# Sheet3.net
KiCad netlist of a schematic drawn in Altium Designer
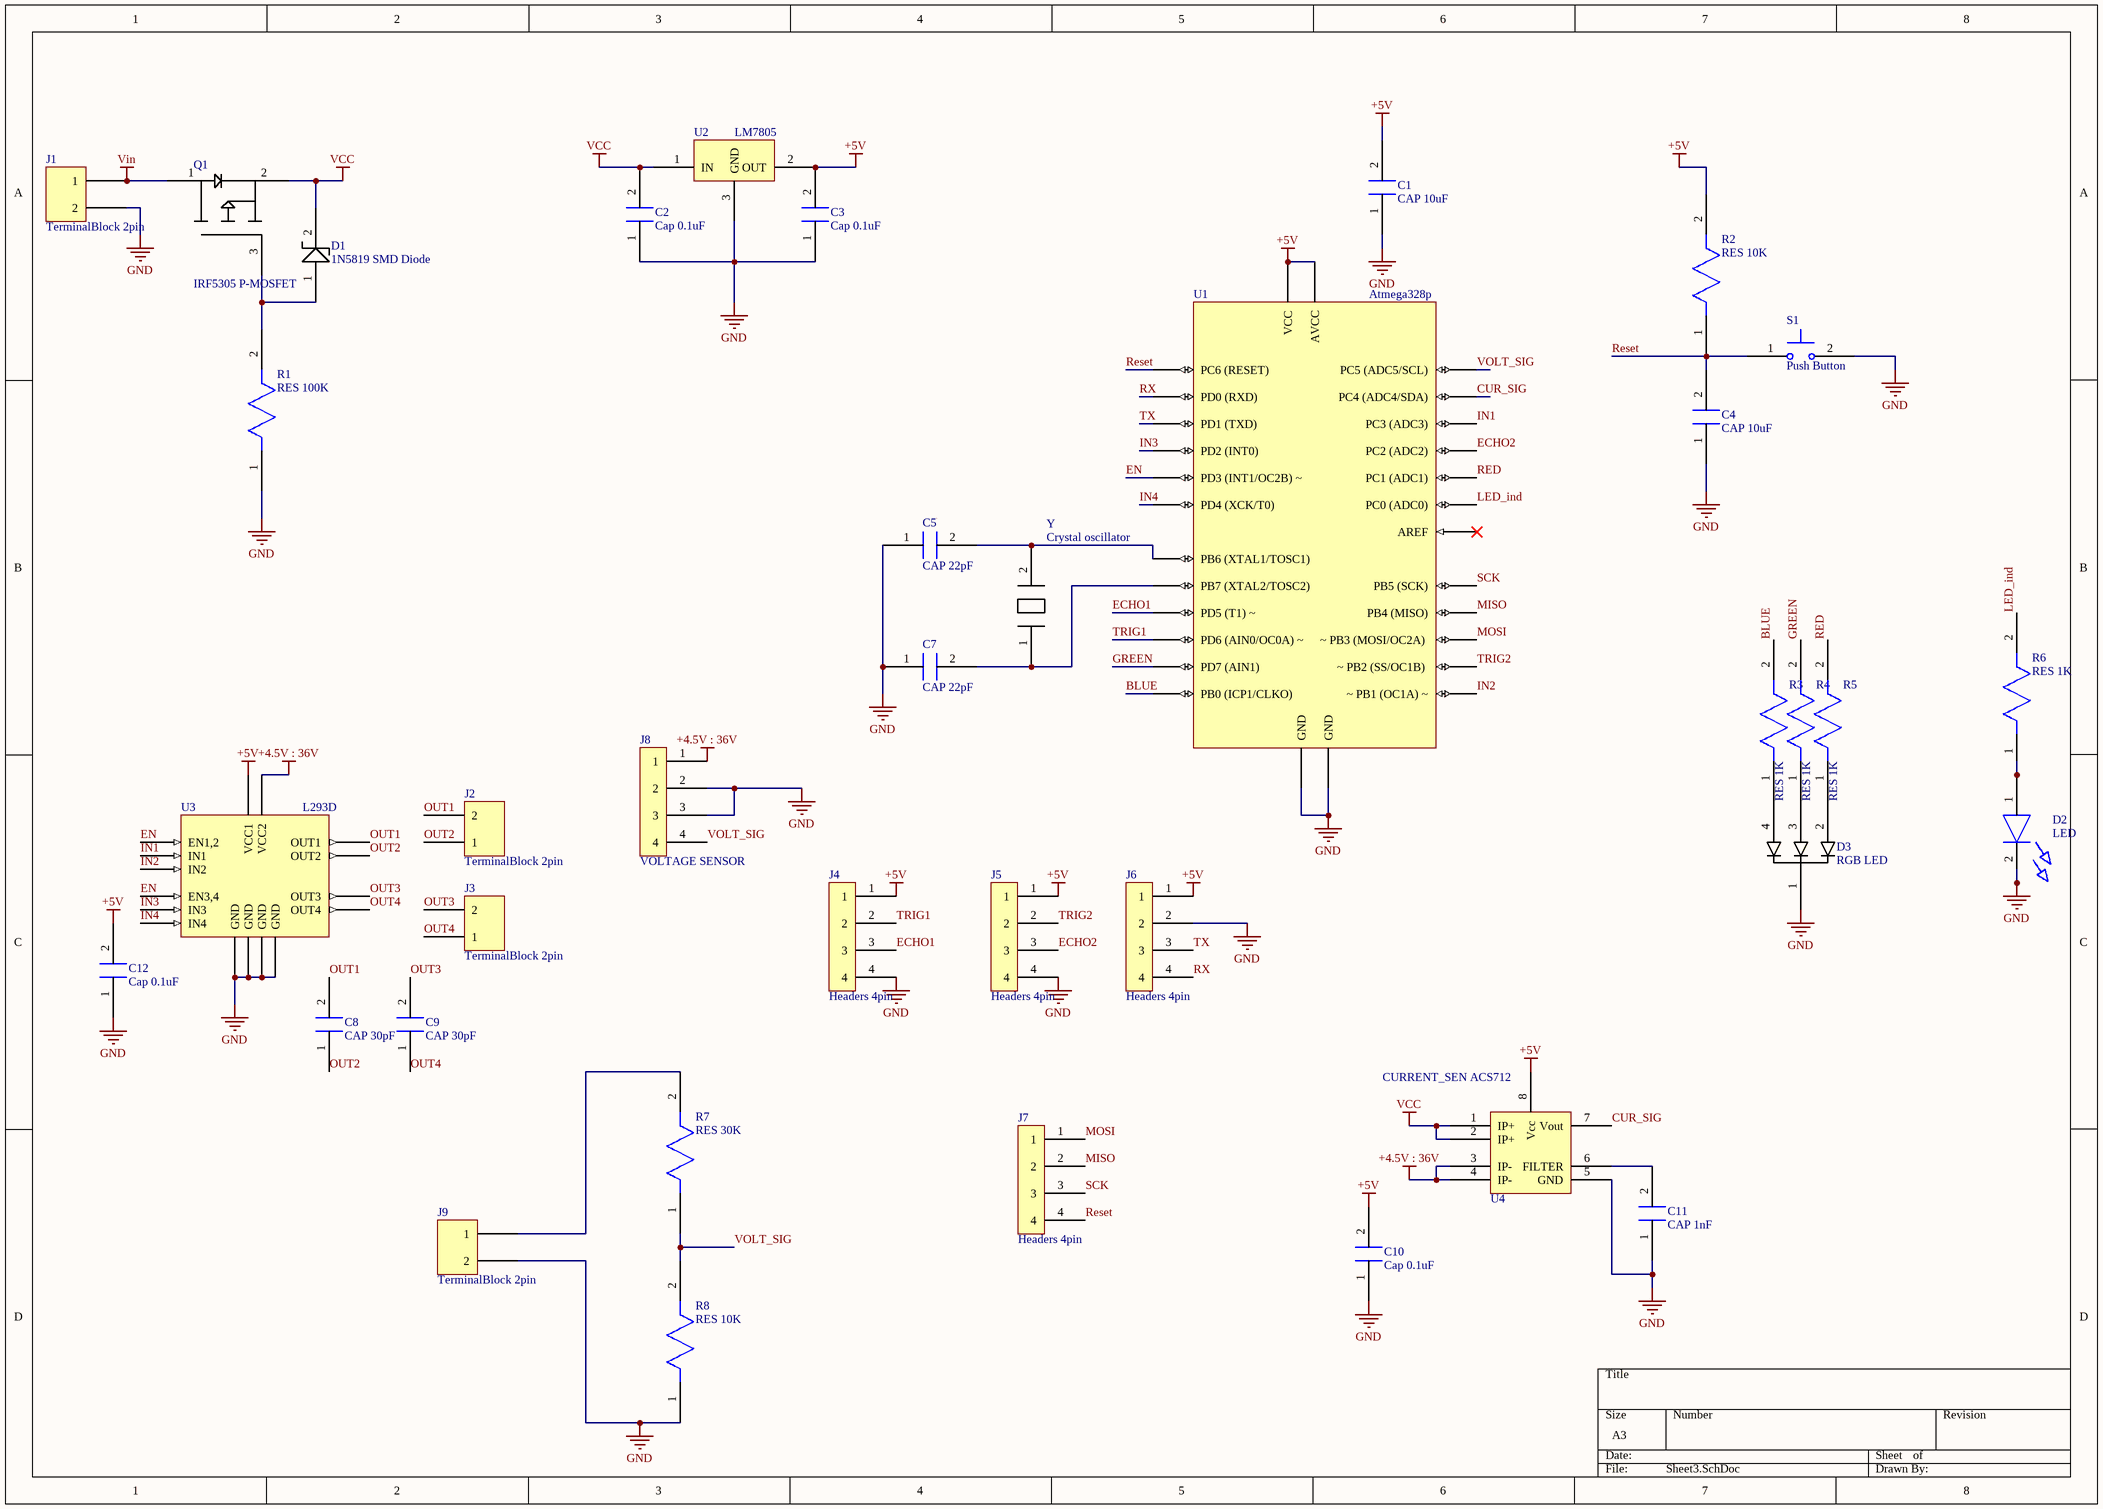
[diagram p0: Sheet3.SchDoc]

(export (version "E")
  (design (tool "Eeschema 10.0.6"))
  (components
    (comp (ref "C1") (value "CAP 10uF") (footprint "Cap 10uF") (libsource (lib "Schlib1") (part "CAP 10uF")))
    (comp (ref "C2")
      (value "Cap 0.1uF")
      (footprint "CAP 0.1uF")
      (libsource (lib "Schlib1") (part "Cap 0.1uF"))
    )
    (comp (ref "C3")
      (value "Cap 0.1uF")
      (footprint "CAP 0.1uF")
      (libsource (lib "Schlib1") (part "Cap 0.1uF"))
    )
    (comp (ref "C4") (value "CAP 10uF") (footprint "Cap 10uF") (libsource (lib "Schlib1") (part "CAP 10uF")))
    (comp (ref "C5") (value "CAP 22pF") (footprint "Cap 22pF") (libsource (lib "Schlib1") (part "CAP 22pF")))
    (comp (ref "C7") (value "CAP 22pF") (footprint "Cap 22pF") (libsource (lib "Schlib1") (part "CAP 22pF")))
    (comp (ref "C8") (value "CAP 30pF") (footprint "CAP 30pF") (libsource (lib "Schlib1") (part "CAP 30pF")))
    (comp (ref "C9") (value "CAP 30pF") (footprint "CAP 30pF") (libsource (lib "Schlib1") (part "CAP 30pF")))
    (comp (ref "C10")
      (value "Cap 0.1uF")
      (footprint "CAP 0.1uF")
      (libsource (lib "Schlib1") (part "Cap 0.1uF"))
    )
    (comp (ref "C11") (value "CAP 1nF") (footprint "CAP 1nF") (libsource (lib "Schlib1") (part "CAP 1nF")))
    (comp (ref "C12")
      (value "Cap 0.1uF")
      (footprint "CAP 0.1uF")
      (libsource (lib "Schlib1") (part "Cap 0.1uF"))
    )
    (comp (ref "D1")
      (value "1N5819 SMD Diode")
      (footprint "1N5819 SMD Diode")
      (libsource (lib "Schlib1") (part "1N5819 SMD Diode"))
    )
    (comp (ref "D2") (value "LED") (footprint "LED") (libsource (lib "Schlib1") (part "LED")))
    (comp (ref "D3") (value "RGB LED") (footprint "RGB LED") (libsource (lib "Schlib1") (part "RGB LED")))
    (comp (ref "J1")
      (value "TerminalBlock 2pin")
      (footprint "Terminal Block 2pin")
      (libsource (lib "Schlib1") (part "TerminalBlock 2pin"))
    )
    (comp (ref "J2")
      (value "TerminalBlock 2pin")
      (footprint "Terminal Block 2pin")
      (libsource (lib "") (part "TerminalBlock 2pin_1"))
    )
    (comp (ref "J3")
      (value "TerminalBlock 2pin")
      (footprint "Terminal Block 2pin")
      (libsource (lib "") (part "TerminalBlock 2pin_1"))
    )
    (comp (ref "J4")
      (value "Headers 4pin")
      (footprint "Header 4pin")
      (libsource (lib "Schlib1") (part "Headers 4pin"))
    )
    (comp (ref "J5")
      (value "Headers 4pin")
      (footprint "Header 4pin")
      (libsource (lib "Schlib1") (part "Headers 4pin"))
    )
    (comp (ref "J6")
      (value "Headers 4pin")
      (footprint "Header 4pin")
      (libsource (lib "Schlib1") (part "Headers 4pin"))
    )
    (comp (ref "J7")
      (value "Headers 4pin")
      (footprint "Header 4pin")
      (libsource (lib "Schlib1") (part "Headers 4pin"))
    )
    (comp (ref "J8")
      (value "VOLTAGE SENSOR")
      (footprint "Header 4pin")
      (libsource (lib "Schlib1") (part "Headers 4pin"))
    )
    (comp (ref "J9")
      (value "TerminalBlock 2pin")
      (footprint "Terminal Block 2pin")
      (libsource (lib "Schlib1") (part "TerminalBlock 2pin"))
    )
    (comp (ref "Q1")
      (value "IRF5305 P-MOSFET")
      (footprint "IRF5305")
      (libsource (lib "Schlib1") (part "IRF5305 P-MOSFET"))
    )
    (comp (ref "R1") (value "RES 100K") (footprint "Res100K") (libsource (lib "Schlib1") (part "RES 100K")))
    (comp (ref "R2") (value "RES 10K") (footprint "Res10K") (libsource (lib "Schlib1") (part "RES 10K")))
    (comp (ref "R3") (value "RES 1K") (footprint "Res 1K") (libsource (lib "Schlib1") (part "RES 1K")))
    (comp (ref "R4") (value "RES 1K") (footprint "Res 1K") (libsource (lib "Schlib1") (part "RES 1K")))
    (comp (ref "R5") (value "RES 1K") (footprint "Res 1K") (libsource (lib "Schlib1") (part "RES 1K")))
    (comp (ref "R6") (value "RES 1K") (footprint "Res 1K") (libsource (lib "Schlib1") (part "RES 1K")))
    (comp (ref "R7") (value "RES 30K") (footprint "Res100K") (libsource (lib "Schlib1") (part "RES 100K")))
    (comp (ref "R8") (value "RES 10K") (footprint "Res10K") (libsource (lib "Schlib1") (part "RES 10K")))
    (comp (ref "S1")
      (value "Push Button")
      (footprint "Push Button")
      (libsource (lib "Schlib1") (part "Push Button"))
    )
    (comp (ref "U1")
      (value "Atmega328p")
      (footprint "ATMega 328 P-PU - duplicate")
      (libsource (lib "Schlib1") (part "Atmega328p"))
    )
    (comp (ref "U2") (value "LM7805") (footprint "LM7805") (libsource (lib "Schlib1") (part "LM7805")))
    (comp (ref "U3") (value "L293D") (footprint "L293D") (libsource (lib "Schlib1") (part "L293D")))
    (comp (ref "U4")
      (value "CURRENT_SEN ACS712")
      (footprint "Cuurent_sens")
      (libsource (lib "Schlib1") (part "CURRENT_MOD ACS712"))
    )
    (comp (ref "Y")
      (value "Crystal oscillator")
      (footprint "Crrystal 16MHZ")
      (libsource (lib "Schlib1") (part "Crystal oscillator"))
    )
  )
  (nets
    (net (code "1") (name "+4.5V : 36V") (class "Default")
      (node (ref "J8") (pin "1") (pinfunction "1_1") (pintype "passive"))
      (node (ref "U3") (pin "8") (pinfunction "VCC2_8") (pintype "power_in"))
      (node (ref "U4") (pin "3") (pinfunction "IP-_3") (pintype "passive"))
      (node (ref "U4") (pin "4") (pinfunction "IP-_4") (pintype "passive"))
    )
    (net (code "2") (name "+5V") (class "Default")
      (node (ref "C1") (pin "2") (pinfunction "2_2") (pintype "passive"))
      (node (ref "C10") (pin "2") (pinfunction "2_2") (pintype "passive"))
      (node (ref "C12") (pin "2") (pinfunction "2_2") (pintype "passive"))
      (node (ref "C3") (pin "2") (pinfunction "2_2") (pintype "passive"))
      (node (ref "J4") (pin "1") (pinfunction "1_1") (pintype "passive"))
      (node (ref "J5") (pin "1") (pinfunction "1_1") (pintype "passive"))
      (node (ref "J6") (pin "1") (pinfunction "1_1") (pintype "passive"))
      (node (ref "R2") (pin "2") (pinfunction "4_2") (pintype "passive"))
      (node (ref "U1") (pin "20") (pinfunction "AVCC_20") (pintype "passive"))
      (node (ref "U1") (pin "7") (pinfunction "VCC_7") (pintype "passive"))
      (node (ref "U2") (pin "2") (pinfunction "OUT_2") (pintype "passive"))
      (node (ref "U3") (pin "16") (pinfunction "VCC1_16") (pintype "power_in"))
      (node (ref "U4") (pin "8") (pinfunction "Vcc_8") (pintype "passive"))
    )
    (net (code "4") (name "/BLUE") (class "Default")
      (node (ref "R3") (pin "2") (pinfunction "4_2") (pintype "passive"))
      (node (ref "U1") (pin "14") (pinfunction "PB0_(ICP1/CLKO)_14") (pintype "bidirectional"))
    )
    (net (code "5") (name "/CUR_SIG") (class "Default")
      (node (ref "U1") (pin "27") (pinfunction "PC4_(ADC4/SDA)_27") (pintype "bidirectional"))
      (node (ref "U4") (pin "7") (pinfunction "Vout_7") (pintype "passive"))
    )
    (net (code "6") (name "/ECHO1") (class "Default")
      (node (ref "J4") (pin "3") (pinfunction "3_3") (pintype "passive"))
      (node (ref "U1") (pin "11") (pinfunction "PD5_(T1)_~_11") (pintype "bidirectional"))
    )
    (net (code "7") (name "/ECHO2") (class "Default")
      (node (ref "J5") (pin "3") (pinfunction "3_3") (pintype "passive"))
      (node (ref "U1") (pin "25") (pinfunction "PC2_(ADC2)_25") (pintype "bidirectional"))
    )
    (net (code "8") (name "/EN") (class "Default")
      (node (ref "U1") (pin "5") (pinfunction "PD3_(INT1/OC2B)_~_5") (pintype "bidirectional"))
      (node (ref "U3") (pin "1") (pinfunction "EN1,2_1") (pintype "input"))
      (node (ref "U3") (pin "9") (pinfunction "EN3,4_9") (pintype "input"))
    )
    (net (code "9") (name "/GREEN") (class "Default")
      (node (ref "R4") (pin "2") (pinfunction "4_2") (pintype "passive"))
      (node (ref "U1") (pin "13") (pinfunction "PD7_(AIN1)_13") (pintype "bidirectional"))
    )
    (net (code "10") (name "/IN1") (class "Default")
      (node (ref "U1") (pin "26") (pinfunction "PC3_(ADC3)_26") (pintype "bidirectional"))
      (node (ref "U3") (pin "2") (pinfunction "IN1_2") (pintype "input"))
    )
    (net (code "11") (name "/IN2") (class "Default")
      (node (ref "U1") (pin "15") (pinfunction "~_PB1_(OC1A)_~_15") (pintype "bidirectional"))
      (node (ref "U3") (pin "7") (pinfunction "IN2_7") (pintype "input"))
    )
    (net (code "12") (name "/IN3") (class "Default")
      (node (ref "U1") (pin "4") (pinfunction "PD2_(INT0)_4") (pintype "bidirectional"))
      (node (ref "U3") (pin "10") (pinfunction "IN3_10") (pintype "input"))
    )
    (net (code "13") (name "/IN4") (class "Default")
      (node (ref "U1") (pin "6") (pinfunction "PD4_(XCK/T0)_6") (pintype "bidirectional"))
      (node (ref "U3") (pin "15") (pinfunction "IN4_15") (pintype "input"))
    )
    (net (code "14") (name "/LED_ind") (class "Default")
      (node (ref "R6") (pin "2") (pinfunction "4_2") (pintype "passive"))
      (node (ref "U1") (pin "23") (pinfunction "PC0_(ADC0)_23") (pintype "bidirectional"))
    )
    (net (code "15") (name "/MISO") (class "Default")
      (node (ref "J7") (pin "2") (pinfunction "2_2") (pintype "passive"))
      (node (ref "U1") (pin "18") (pinfunction "PB4_(MISO)_18") (pintype "bidirectional"))
    )
    (net (code "16") (name "/MOSI") (class "Default")
      (node (ref "J7") (pin "1") (pinfunction "1_1") (pintype "passive"))
      (node (ref "U1") (pin "17") (pinfunction "~_PB3_(MOSI/OC2A)_17") (pintype "bidirectional"))
    )
    (net (code "17") (name "/OUT1") (class "Default")
      (node (ref "C8") (pin "2") (pinfunction "2_2") (pintype "passive"))
      (node (ref "J2") (pin "2") (pinfunction "2_2") (pintype "passive"))
      (node (ref "U3") (pin "3") (pinfunction "OUT1_3") (pintype "output"))
    )
    (net (code "18") (name "/OUT2") (class "Default")
      (node (ref "C8") (pin "1") (pinfunction "1_1") (pintype "passive"))
      (node (ref "J2") (pin "1") (pinfunction "1_1") (pintype "passive"))
      (node (ref "U3") (pin "6") (pinfunction "OUT2_6") (pintype "output"))
    )
    (net (code "19") (name "/OUT3") (class "Default")
      (node (ref "C9") (pin "2") (pinfunction "2_2") (pintype "passive"))
      (node (ref "J3") (pin "2") (pinfunction "2_2") (pintype "passive"))
      (node (ref "U3") (pin "11") (pinfunction "OUT3_11") (pintype "output"))
    )
    (net (code "20") (name "/OUT4") (class "Default")
      (node (ref "C9") (pin "1") (pinfunction "1_1") (pintype "passive"))
      (node (ref "J3") (pin "1") (pinfunction "1_1") (pintype "passive"))
      (node (ref "U3") (pin "14") (pinfunction "OUT4_14") (pintype "output"))
    )
    (net (code "21") (name "/RED") (class "Default")
      (node (ref "R5") (pin "2") (pinfunction "4_2") (pintype "passive"))
      (node (ref "U1") (pin "24") (pinfunction "PC1_(ADC1)_24") (pintype "bidirectional"))
    )
    (net (code "22") (name "/RX") (class "Default")
      (node (ref "J6") (pin "4") (pinfunction "4_4") (pintype "passive"))
      (node (ref "U1") (pin "2") (pinfunction "PD0_(RXD)_2") (pintype "bidirectional"))
    )
    (net (code "23") (name "/Reset") (class "Default")
      (node (ref "C4") (pin "2") (pinfunction "2_2") (pintype "passive"))
      (node (ref "J7") (pin "4") (pinfunction "4_4") (pintype "passive"))
      (node (ref "R2") (pin "1") (pinfunction "3_1") (pintype "passive"))
      (node (ref "S1") (pin "1") (pinfunction "76_1") (pintype "passive"))
      (node (ref "U1") (pin "1") (pinfunction "PC6_(RESET)_1") (pintype "bidirectional"))
    )
    (net (code "24") (name "/SCK") (class "Default")
      (node (ref "J7") (pin "3") (pinfunction "3_3") (pintype "passive"))
      (node (ref "U1") (pin "19") (pinfunction "PB5_(SCK)_19") (pintype "bidirectional"))
    )
    (net (code "25") (name "/TRIG1") (class "Default")
      (node (ref "J4") (pin "2") (pinfunction "2_2") (pintype "passive"))
      (node (ref "U1") (pin "12") (pinfunction "PD6_(AIN0/OC0A)_~_12") (pintype "bidirectional"))
    )
    (net (code "26") (name "/TRIG2") (class "Default")
      (node (ref "J5") (pin "2") (pinfunction "2_2") (pintype "passive"))
      (node (ref "U1") (pin "16") (pinfunction "~_PB2_(SS/OC1B)_16") (pintype "bidirectional"))
    )
    (net (code "27") (name "/TX") (class "Default")
      (node (ref "J6") (pin "3") (pinfunction "3_3") (pintype "passive"))
      (node (ref "U1") (pin "3") (pinfunction "PD1_(TXD)_3") (pintype "bidirectional"))
    )
    (net (code "28") (name "/VOLT_SIG") (class "Default")
      (node (ref "J8") (pin "4") (pinfunction "4_4") (pintype "passive"))
      (node (ref "R7") (pin "1") (pinfunction "3_1") (pintype "passive"))
      (node (ref "R8") (pin "2") (pinfunction "4_2") (pintype "passive"))
      (node (ref "U1") (pin "28") (pinfunction "PC5_(ADC5/SCL)_28") (pintype "bidirectional"))
    )
    (net (code "29") (name "GND") (class "Default")
      (node (ref "C1") (pin "1") (pinfunction "1_1") (pintype "passive"))
      (node (ref "C10") (pin "1") (pinfunction "1_1") (pintype "passive"))
      (node (ref "C11") (pin "1") (pinfunction "1_1") (pintype "passive"))
      (node (ref "C12") (pin "1") (pinfunction "1_1") (pintype "passive"))
      (node (ref "C2") (pin "1") (pinfunction "1_1") (pintype "passive"))
      (node (ref "C3") (pin "1") (pinfunction "1_1") (pintype "passive"))
      (node (ref "C4") (pin "1") (pinfunction "1_1") (pintype "passive"))
      (node (ref "C5") (pin "1") (pinfunction "1_1") (pintype "passive"))
      (node (ref "C7") (pin "1") (pinfunction "1_1") (pintype "passive"))
      (node (ref "D2") (pin "2") (pinfunction "6_2") (pintype "passive"))
      (node (ref "D3") (pin "1") (pinfunction "(-)_1") (pintype "passive"))
      (node (ref "J1") (pin "2") (pinfunction "2_2") (pintype "passive"))
      (node (ref "J4") (pin "4") (pinfunction "4_4") (pintype "passive"))
      (node (ref "J5") (pin "4") (pinfunction "4_4") (pintype "passive"))
      (node (ref "J6") (pin "2") (pinfunction "2_2") (pintype "passive"))
      (node (ref "J8") (pin "2") (pinfunction "2_2") (pintype "passive"))
      (node (ref "J8") (pin "3") (pinfunction "3_3") (pintype "passive"))
      (node (ref "J9") (pin "2") (pinfunction "2_2") (pintype "passive"))
      (node (ref "R1") (pin "1") (pinfunction "3_1") (pintype "passive"))
      (node (ref "R8") (pin "1") (pinfunction "3_1") (pintype "passive"))
      (node (ref "S1") (pin "2") (pinfunction "77_2") (pintype "passive"))
      (node (ref "U1") (pin "22") (pinfunction "GND_22") (pintype "passive"))
      (node (ref "U1") (pin "8") (pinfunction "GND_8") (pintype "passive"))
      (node (ref "U2") (pin "3") (pinfunction "GND_3") (pintype "power_in"))
      (node (ref "U3") (pin "12") (pinfunction "GND_12") (pintype "power_in"))
      (node (ref "U3") (pin "13") (pinfunction "GND_13") (pintype "power_in"))
      (node (ref "U3") (pin "4") (pinfunction "GND_4") (pintype "power_in"))
      (node (ref "U3") (pin "5") (pinfunction "GND_5") (pintype "power_in"))
      (node (ref "U4") (pin "5") (pinfunction "GND_5") (pintype "passive"))
    )
    (net (code "30") (name "Net-(D2-7)") (class "Default")
      (node (ref "D2") (pin "1") (pinfunction "7_1") (pintype "passive"))
      (node (ref "R6") (pin "1") (pinfunction "3_1") (pintype "passive"))
    )
    (net (code "31") (name "Net-(D3-B)") (class "Default")
      (node (ref "D3") (pin "4") (pinfunction "B_4") (pintype "passive"))
      (node (ref "R3") (pin "1") (pinfunction "3_1") (pintype "passive"))
    )
    (net (code "32") (name "Net-(D3-G)") (class "Default")
      (node (ref "D3") (pin "3") (pinfunction "G_3") (pintype "passive"))
      (node (ref "R4") (pin "1") (pinfunction "3_1") (pintype "passive"))
    )
    (net (code "33") (name "Net-(D3-R)") (class "Default")
      (node (ref "D3") (pin "2") (pinfunction "R_2") (pintype "passive"))
      (node (ref "R5") (pin "1") (pinfunction "3_1") (pintype "passive"))
    )
    (net (code "34") (name "Net-(Q1-G)") (class "Default")
      (node (ref "D1") (pin "1") (pinfunction "1_1") (pintype "passive"))
      (node (ref "Q1") (pin "3") (pinfunction "G_3") (pintype "passive"))
      (node (ref "R1") (pin "2") (pinfunction "4_2") (pintype "passive"))
    )
    (net (code "35") (name "Net-(R7-4)") (class "Default")
      (node (ref "J9") (pin "1") (pinfunction "1_1") (pintype "passive"))
      (node (ref "R7") (pin "2") (pinfunction "4_2") (pintype "passive"))
    )
    (net (code "36") (name "Net-(U1-PB6_(XTAL1{slash}TOSC1))") (class "Default")
      (node (ref "C5") (pin "2") (pinfunction "2_2") (pintype "passive"))
      (node (ref "U1") (pin "9") (pinfunction "PB6_(XTAL1/TOSC1)_9") (pintype "bidirectional"))
      (node (ref "Y") (pin "2") (pinfunction "2_2") (pintype "passive"))
    )
    (net (code "37") (name "Net-(U1-PB7_(XTAL2{slash}TOSC2))") (class "Default")
      (node (ref "C7") (pin "2") (pinfunction "2_2") (pintype "passive"))
      (node (ref "U1") (pin "10") (pinfunction "PB7_(XTAL2/TOSC2)_10") (pintype "bidirectional"))
      (node (ref "Y") (pin "1") (pinfunction "1_1") (pintype "passive"))
    )
    (net (code "38") (name "Net-(U4-FILTER)") (class "Default")
      (node (ref "C11") (pin "2") (pinfunction "2_2") (pintype "passive"))
      (node (ref "U4") (pin "6") (pinfunction "FILTER_6") (pintype "passive"))
    )
    (net (code "39") (name "VCC") (class "Default")
      (node (ref "C2") (pin "2") (pinfunction "2_2") (pintype "passive"))
      (node (ref "D1") (pin "2") (pinfunction "2_2") (pintype "passive"))
      (node (ref "Q1") (pin "2") (pinfunction "S_2") (pintype "passive"))
      (node (ref "U2") (pin "1") (pinfunction "IN_1") (pintype "passive"))
      (node (ref "U4") (pin "1") (pinfunction "IP+_1") (pintype "passive"))
      (node (ref "U4") (pin "2") (pinfunction "IP+_2") (pintype "passive"))
    )
    (net (code "40") (name "Vin") (class "Default")
      (node (ref "J1") (pin "1") (pinfunction "1_1") (pintype "passive"))
      (node (ref "Q1") (pin "1") (pinfunction "D_1") (pintype "passive"))
    )
    (net (code "41") (name "unconnected-(U1-AREF-Pad21)") (class "Default")
      (node (ref "U1") (pin "21") (pinfunction "AREF_21") (pintype "input+no_connect"))
    )
  )
)
